# main_Schematic.net
KiCad netlist of a schematic drawn in Altium Designer
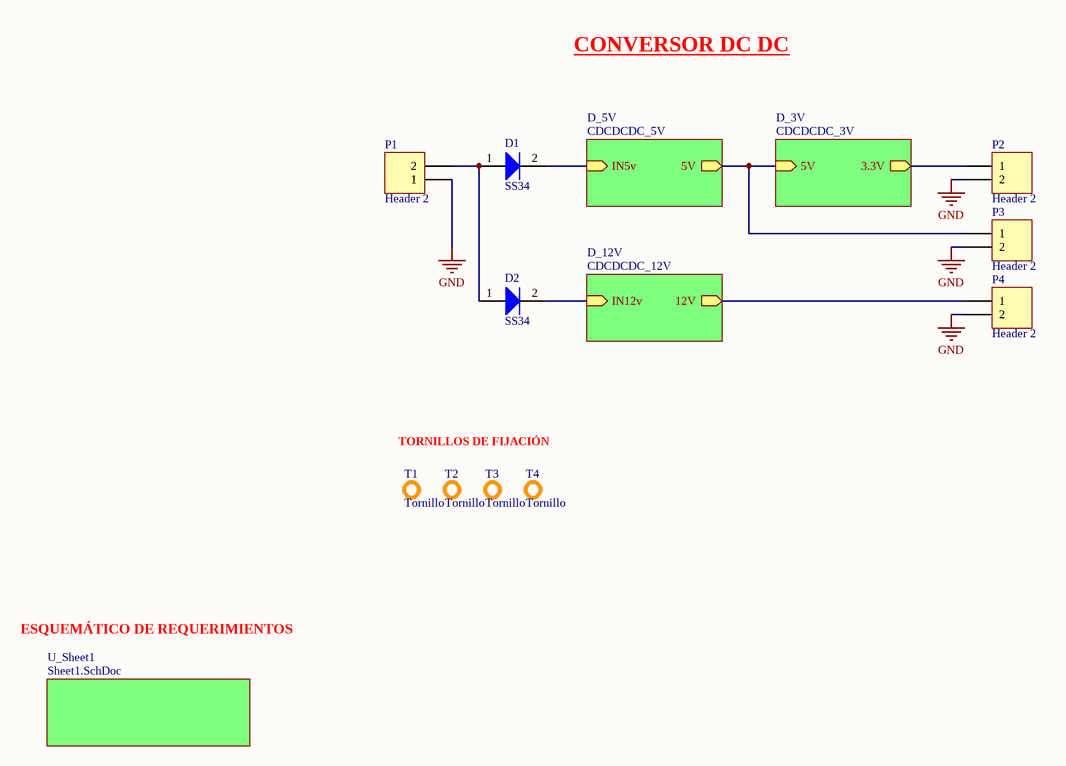
[diagram p0: main_Schematic.SchDoc]

(export (version "E")
  (design (tool "Eeschema 10.0.6"))
  (components
    (comp (ref "D1")
      (value "SS34")
      (footprint "SMC")
      (description "Default Diode")
      (fields (field (name "PUBLISHER") "Altium Limited"))
      (libsource (lib "Miscellaneous Devices") (part "Diode"))
    )
    (comp (ref "D2")
      (value "SS34")
      (footprint "SMC")
      (description "Default Diode")
      (fields (field (name "PUBLISHER") "Altium Limited"))
      (libsource (lib "Miscellaneous Devices") (part "Diode"))
    )
    (comp (ref "P1")
      (value "Header 2")
      (footprint "HDR1X2")
      (description "Header, 2-Pin")
      (fields (field (name "PUBLISHER") "Altium Limited"))
      (libsource (lib "") (part "Header 2_1"))
    )
    (comp (ref "P2")
      (value "Header 2")
      (footprint "HDR1X2")
      (description "Header, 2-Pin")
      (fields (field (name "PUBLISHER") "Altium Limited"))
      (libsource (lib "Miscellaneous Connectors") (part "Header 2"))
    )
    (comp (ref "P3")
      (value "Header 2")
      (footprint "HDR1X2")
      (description "Header, 2-Pin")
      (fields (field (name "PUBLISHER") "Altium Limited"))
      (libsource (lib "Miscellaneous Connectors") (part "Header 2"))
    )
    (comp (ref "P4")
      (value "Header 2")
      (footprint "HDR1X2")
      (description "Header, 2-Pin")
      (fields (field (name "PUBLISHER") "Altium Limited"))
      (libsource (lib "Miscellaneous Connectors") (part "Header 2"))
    )
    (comp (ref "T1")
      (value "Tornillo")
      (footprint "Tornilo - duplicate")
      (libsource (lib "Schlib1") (part "Tornillo"))
    )
    (comp (ref "T2")
      (value "Tornillo")
      (footprint "Tornilo - duplicate")
      (libsource (lib "Schlib1") (part "Tornillo"))
    )
    (comp (ref "T3")
      (value "Tornillo")
      (footprint "Tornilo - duplicate")
      (libsource (lib "Schlib1") (part "Tornillo"))
    )
    (comp (ref "T4")
      (value "Tornillo")
      (footprint "Tornilo - duplicate")
      (libsource (lib "Schlib1") (part "Tornillo"))
    )
  )
  (nets
    (net (code "1") (name "/3.3V") (class "Default")
      (node (ref "P2") (pin "1") (pinfunction "1_1") (pintype "passive"))
    )
    (net (code "2") (name "/5V") (class "Default")
      (node (ref "P3") (pin "1") (pinfunction "1_1") (pintype "passive"))
    )
    (net (code "3") (name "/12V") (class "Default")
      (node (ref "P4") (pin "1") (pinfunction "1_1") (pintype "passive"))
    )
    (net (code "4") (name "/IN5v") (class "Default")
      (node (ref "D1") (pin "2") (pinfunction "K_2") (pintype "passive"))
    )
    (net (code "5") (name "/IN12v") (class "Default")
      (node (ref "D2") (pin "2") (pinfunction "K_2") (pintype "passive"))
    )
    (net (code "6") (name "GND") (class "Default")
      (node (ref "P1") (pin "1") (pinfunction "1_1") (pintype "passive"))
      (node (ref "P2") (pin "2") (pinfunction "2_2") (pintype "passive"))
      (node (ref "P3") (pin "2") (pinfunction "2_2") (pintype "passive"))
      (node (ref "P4") (pin "2") (pinfunction "2_2") (pintype "passive"))
    )
    (net (code "7") (name "Net-(D1-A)") (class "Default")
      (node (ref "D1") (pin "1") (pinfunction "A_1") (pintype "passive"))
      (node (ref "D2") (pin "1") (pinfunction "A_1") (pintype "passive"))
      (node (ref "P1") (pin "2") (pinfunction "2_2") (pintype "passive"))
    )
  )
)
